# Sheet1.net
KiCad netlist of a schematic drawn in Altium Designer
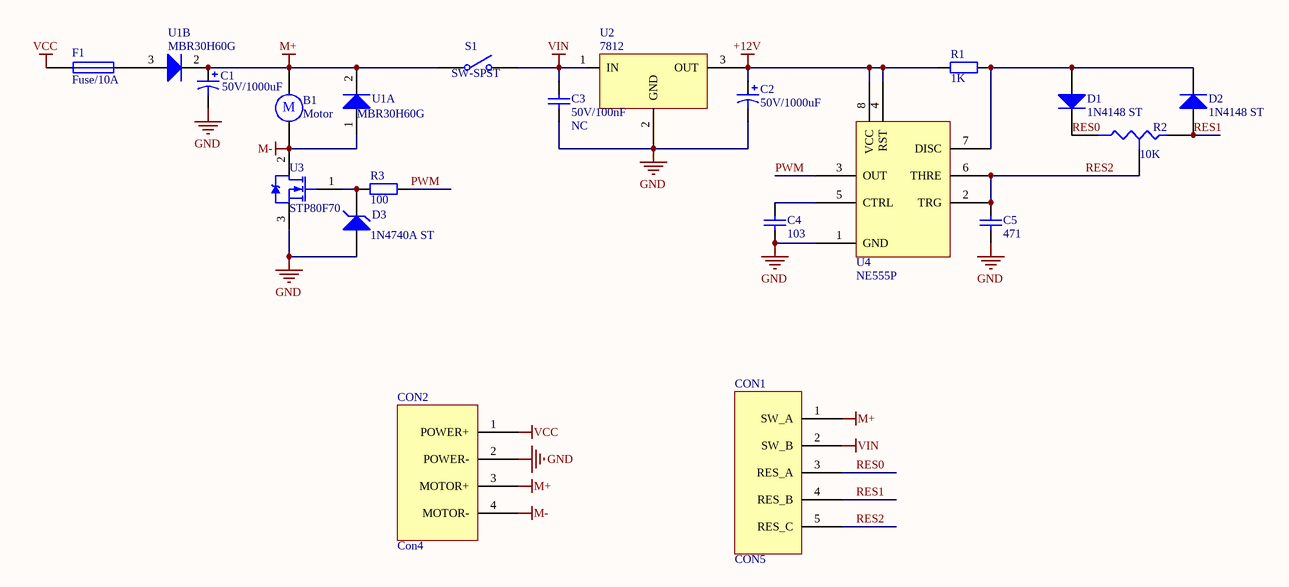
[diagram p0: Sheet1.SchDoc]

(export (version "E")
  (design (tool "Eeschema 10.0.6"))
  (components
    (comp (ref "B1")
      (value "Motor")
      (footprint "RB5-10.5")
      (description "Motor, General Kind")
      (fields (field (name "PUBLISHER") "Altium Limited"))
      (libsource (lib "Miscellaneous Devices") (part "Motor"))
    )
    (comp (ref "C1")
      (value "50V/1000uF")
      (footprint "C0805")
      (description "Polarized Capacitor (Surface Mount)")
      (fields (field (name "PUBLISHER") "Altium Limited"))
      (libsource (lib "Miscellaneous Devices") (part "Cap Pol3"))
    )
    (comp (ref "C2")
      (value "50V/1000uF")
      (footprint "C0805")
      (description "Polarized Capacitor (Surface Mount)")
      (fields (field (name "PUBLISHER") "Altium Limited"))
      (libsource (lib "Miscellaneous Devices") (part "Cap Pol3"))
    )
    (comp (ref "C3")
      (value "50V/100nF")
      (footprint "RAD-0.3")
      (description "Capacitor")
      (fields (field (name "ALTIUM_VALUE") "NC") (field (name "PUBLISHER") "Altium Limited"))
      (libsource (lib "Miscellaneous Devices") (part "Cap"))
    )
    (comp (ref "C4")
      (value "103")
      (footprint "RAD-0.3")
      (description "Capacitor")
      (fields (field (name "PUBLISHER") "Altium Limited"))
      (libsource (lib "Miscellaneous Devices") (part "Cap"))
    )
    (comp (ref "C5")
      (value "471")
      (footprint "RAD-0.3")
      (description "Capacitor")
      (fields (field (name "PUBLISHER") "Altium Limited"))
      (libsource (lib "Miscellaneous Devices") (part "Cap"))
    )
    (comp (ref "CON1") (value "CON5") (libsource (lib "Schlib1") (part "CON5")))
    (comp (ref "CON2") (value "Con4") (libsource (lib "Schlib1") (part "CON4")))
    (comp (ref "D1")
      (value "1N4148 ST")
      (footprint "SMC")
      (description "Default Diode")
      (fields (field (name "PUBLISHER") "Altium Limited"))
      (libsource (lib "Miscellaneous Devices") (part "Diode"))
    )
    (comp (ref "D2")
      (value "1N4148 ST")
      (footprint "SMC")
      (description "Default Diode")
      (fields (field (name "PUBLISHER") "Altium Limited"))
      (libsource (lib "Miscellaneous Devices") (part "Diode"))
    )
    (comp (ref "D3")
      (value "1N4740A ST")
      (footprint "DIODE-0.7")
      (description "Zener Diode")
      (fields (field (name "PUBLISHER") "Altium Limited"))
      (libsource (lib "Miscellaneous Devices") (part "D Zener"))
    )
    (comp (ref "F1")
      (value "Fuse/10A")
      (footprint "PIN-W2/E2.8")
      (description "Fuse")
      (fields (field (name "PUBLISHER") "Altium Limited"))
      (libsource (lib "Miscellaneous Devices") (part "Fuse 1"))
    )
    (comp (ref "R1")
      (value "1K")
      (footprint "AXIAL-0.4")
      (description "Resistor")
      (fields (field (name "PUBLISHER") "Altium Limited"))
      (libsource (lib "Miscellaneous Devices") (part "Res2"))
    )
    (comp (ref "R2")
      (value "10K")
      (footprint "VR3")
      (description "Tapped Resistor")
      (fields (field (name "PUBLISHER") "Altium Limited"))
      (libsource (lib "Miscellaneous Devices") (part "Res Tap"))
    )
    (comp (ref "R3")
      (value "100")
      (footprint "AXIAL-0.4")
      (description "Resistor")
      (fields (field (name "PUBLISHER") "Altium Limited"))
      (libsource (lib "") (part "Res2_1"))
    )
    (comp (ref "S1")
      (value "SW-SPST")
      (footprint "SPST-2")
      (description "Single-Pole, Single-Throw Switch")
      (fields (field (name "PUBLISHER") "Altium Limited"))
      (libsource (lib "Miscellaneous Devices") (part "SW-SPST"))
    )
    (comp (ref "U1")
      (value "MBR30H60G")
      (description "60V, 30A SCHOTTKY")
      (libsource (lib "Schlib1") (part "MBR30H60G"))
    )
    (comp (ref "U2")
      (value "7812")
      (description "POSITIVE VOLTAGE REGULATORS")
      (libsource (lib "Schlib1") (part "7812"))
    )
    (comp (ref "U3")
      (value "STP80F70")
      (description "N-channel 68 V, 0.0082 Ω, 98 A, TO-220 MOSFET")
      (libsource (lib "Schlib1") (part "STP80NF70"))
    )
    (comp (ref "U4")
      (value "NE555P")
      (description "GENERAL PURPOSE SINGLE BIPOLAR TIMERS")
      (libsource (lib "Schlib1") (part "NE555P"))
    )
  )
  (nets
    (net (code "1") (name "+12V") (class "Default")
      (node (ref "C2") (pin "1") (pinfunction "1_1") (pintype "passive"))
      (node (ref "R1") (pin "1") (pinfunction "1_1") (pintype "passive"))
      (node (ref "U2") (pin "3") (pinfunction "OUT_3") (pintype "passive"))
      (node (ref "U4") (pin "4") (pinfunction "RST_4") (pintype "passive"))
      (node (ref "U4") (pin "8") (pinfunction "VCC_8") (pintype "passive"))
    )
    (net (code "2") (name "/PWM") (class "Default")
      (node (ref "R3") (pin "1") (pinfunction "1_1") (pintype "passive"))
      (node (ref "U4") (pin "3") (pinfunction "OUT_3") (pintype "passive"))
    )
    (net (code "3") (name "/RES0") (class "Default")
      (node (ref "CON1") (pin "3") (pinfunction "RES_A_3") (pintype "passive"))
      (node (ref "D1") (pin "2") (pinfunction "K_2") (pintype "passive"))
      (node (ref "R2") (pin "2") (pinfunction "B_2") (pintype "passive"))
    )
    (net (code "4") (name "/RES1") (class "Default")
      (node (ref "CON1") (pin "4") (pinfunction "RES_B_4") (pintype "passive"))
      (node (ref "D2") (pin "1") (pinfunction "A_1") (pintype "passive"))
      (node (ref "R2") (pin "1") (pinfunction "A_1") (pintype "passive"))
    )
    (net (code "5") (name "/RES2") (class "Default")
      (node (ref "C5") (pin "2") (pinfunction "2_2") (pintype "passive"))
      (node (ref "CON1") (pin "5") (pinfunction "RES_C_5") (pintype "passive"))
      (node (ref "R2") (pin "3") (pinfunction "TAP_3") (pintype "passive"))
      (node (ref "U4") (pin "2") (pinfunction "TRG_2") (pintype "passive"))
      (node (ref "U4") (pin "6") (pinfunction "THRE_6") (pintype "passive"))
    )
    (net (code "6") (name "GND") (class "Default")
      (node (ref "C1") (pin "2") (pinfunction "2_2") (pintype "passive"))
      (node (ref "C2") (pin "2") (pinfunction "2_2") (pintype "passive"))
      (node (ref "C3") (pin "1") (pinfunction "1_1") (pintype "passive"))
      (node (ref "C4") (pin "1") (pinfunction "1_1") (pintype "passive"))
      (node (ref "C5") (pin "1") (pinfunction "1_1") (pintype "passive"))
      (node (ref "CON2") (pin "2") (pinfunction "POWER-_2") (pintype "passive"))
      (node (ref "D3") (pin "1") (pinfunction "A_1") (pintype "passive"))
      (node (ref "U2") (pin "2") (pinfunction "GND_2") (pintype "passive"))
      (node (ref "U3") (pin "3") (pinfunction "S_3") (pintype "passive"))
      (node (ref "U4") (pin "1") (pinfunction "GND_1") (pintype "passive"))
    )
    (net (code "7") (name "M+") (class "Default")
      (node (ref "B1") (pin "1") (pinfunction "1_1") (pintype "passive"))
      (node (ref "C1") (pin "1") (pinfunction "1_1") (pintype "passive"))
      (node (ref "CON1") (pin "1") (pinfunction "SW_A_1") (pintype "passive"))
      (node (ref "CON2") (pin "3") (pinfunction "MOTOR+_3") (pintype "passive"))
      (node (ref "S1") (pin "1") (pinfunction "COMMON_1") (pintype "passive"))
      (node (ref "U1") (pin "2") (pinfunction "K_2") (pintype "passive"))
    )
    (net (code "8") (name "M-") (class "Default")
      (node (ref "B1") (pin "2") (pinfunction "2_2") (pintype "passive"))
      (node (ref "CON2") (pin "4") (pinfunction "MOTOR-_4") (pintype "passive"))
      (node (ref "U1") (pin "1") (pinfunction "A_1") (pintype "passive"))
      (node (ref "U3") (pin "2") (pinfunction "D_2") (pintype "passive"))
    )
    (net (code "9") (name "Net-(D1-A)") (class "Default")
      (node (ref "D1") (pin "1") (pinfunction "A_1") (pintype "passive"))
      (node (ref "D2") (pin "2") (pinfunction "K_2") (pintype "passive"))
      (node (ref "R1") (pin "2") (pinfunction "2_2") (pintype "passive"))
      (node (ref "U4") (pin "7") (pinfunction "DISC_7") (pintype "passive"))
    )
    (net (code "10") (name "Net-(D3-K)") (class "Default")
      (node (ref "D3") (pin "2") (pinfunction "K_2") (pintype "passive"))
      (node (ref "R3") (pin "2") (pinfunction "2_2") (pintype "passive"))
      (node (ref "U3") (pin "1") (pinfunction "G_1") (pintype "passive"))
    )
    (net (code "11") (name "Net-(U1B-A)") (class "Default")
      (node (ref "F1") (pin "2") (pinfunction "2_2") (pintype "passive"))
      (node (ref "U1") (pin "3") (pinfunction "A_3") (pintype "passive"))
    )
    (net (code "12") (name "Net-(U4-CTRL)") (class "Default")
      (node (ref "C4") (pin "2") (pinfunction "2_2") (pintype "passive"))
      (node (ref "U4") (pin "5") (pinfunction "CTRL_5") (pintype "passive"))
    )
    (net (code "13") (name "VCC") (class "Default")
      (node (ref "CON2") (pin "1") (pinfunction "POWER+_1") (pintype "passive"))
      (node (ref "F1") (pin "1") (pinfunction "1_1") (pintype "passive"))
    )
    (net (code "14") (name "VIN") (class "Default")
      (node (ref "C3") (pin "2") (pinfunction "2_2") (pintype "passive"))
      (node (ref "CON1") (pin "2") (pinfunction "SW_B_2") (pintype "passive"))
      (node (ref "S1") (pin "2") (pinfunction "NO_2") (pintype "passive"))
      (node (ref "U2") (pin "1") (pinfunction "IN_1") (pintype "passive"))
    )
  )
)
